# osh_bga_test.net
KiCad netlist of a schematic drawn in EAGLE
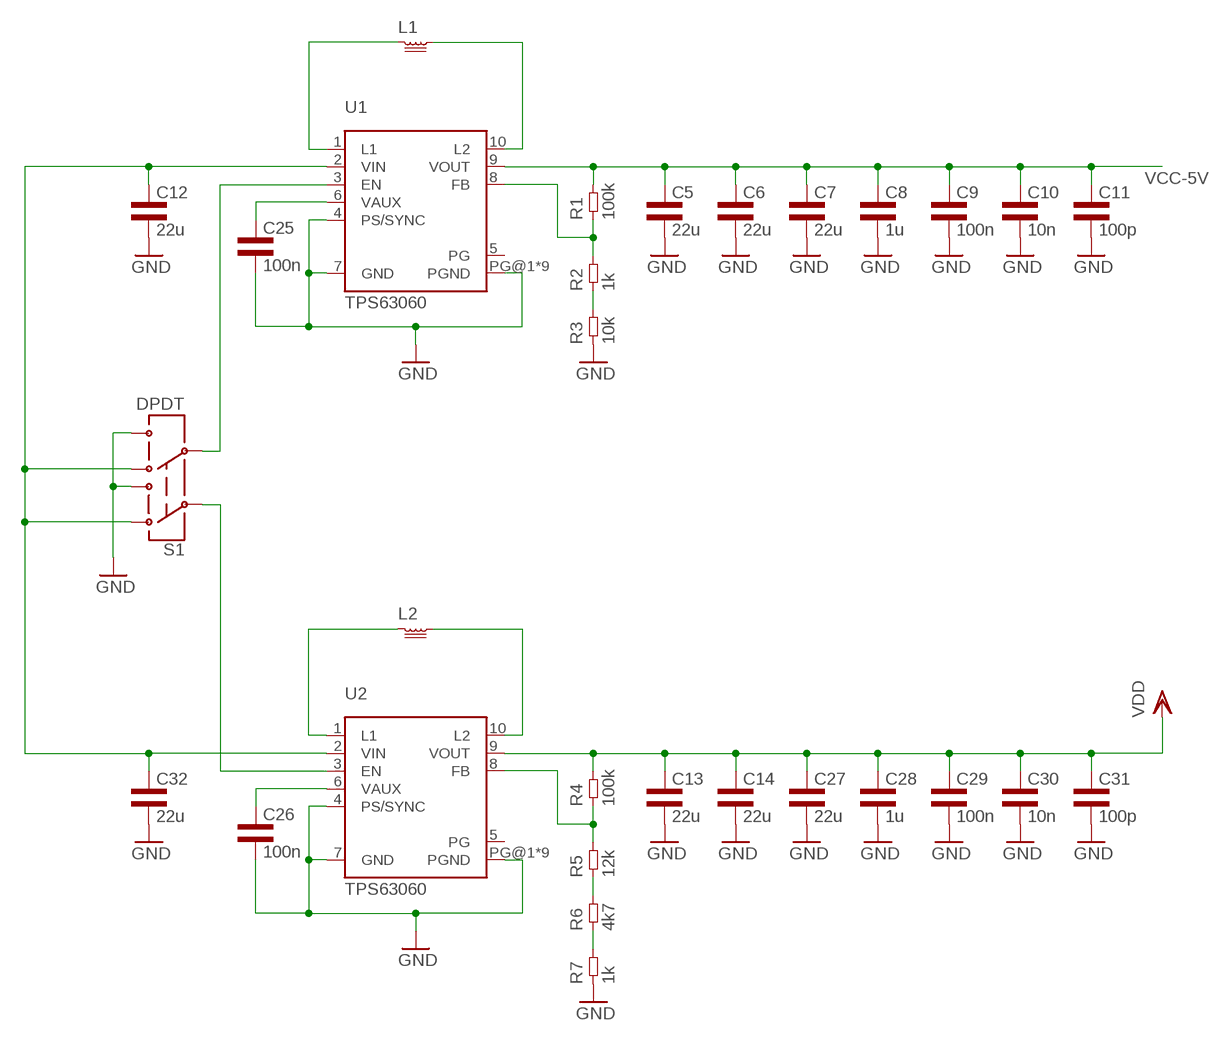
[diagram p0: schematic, sheet 1]
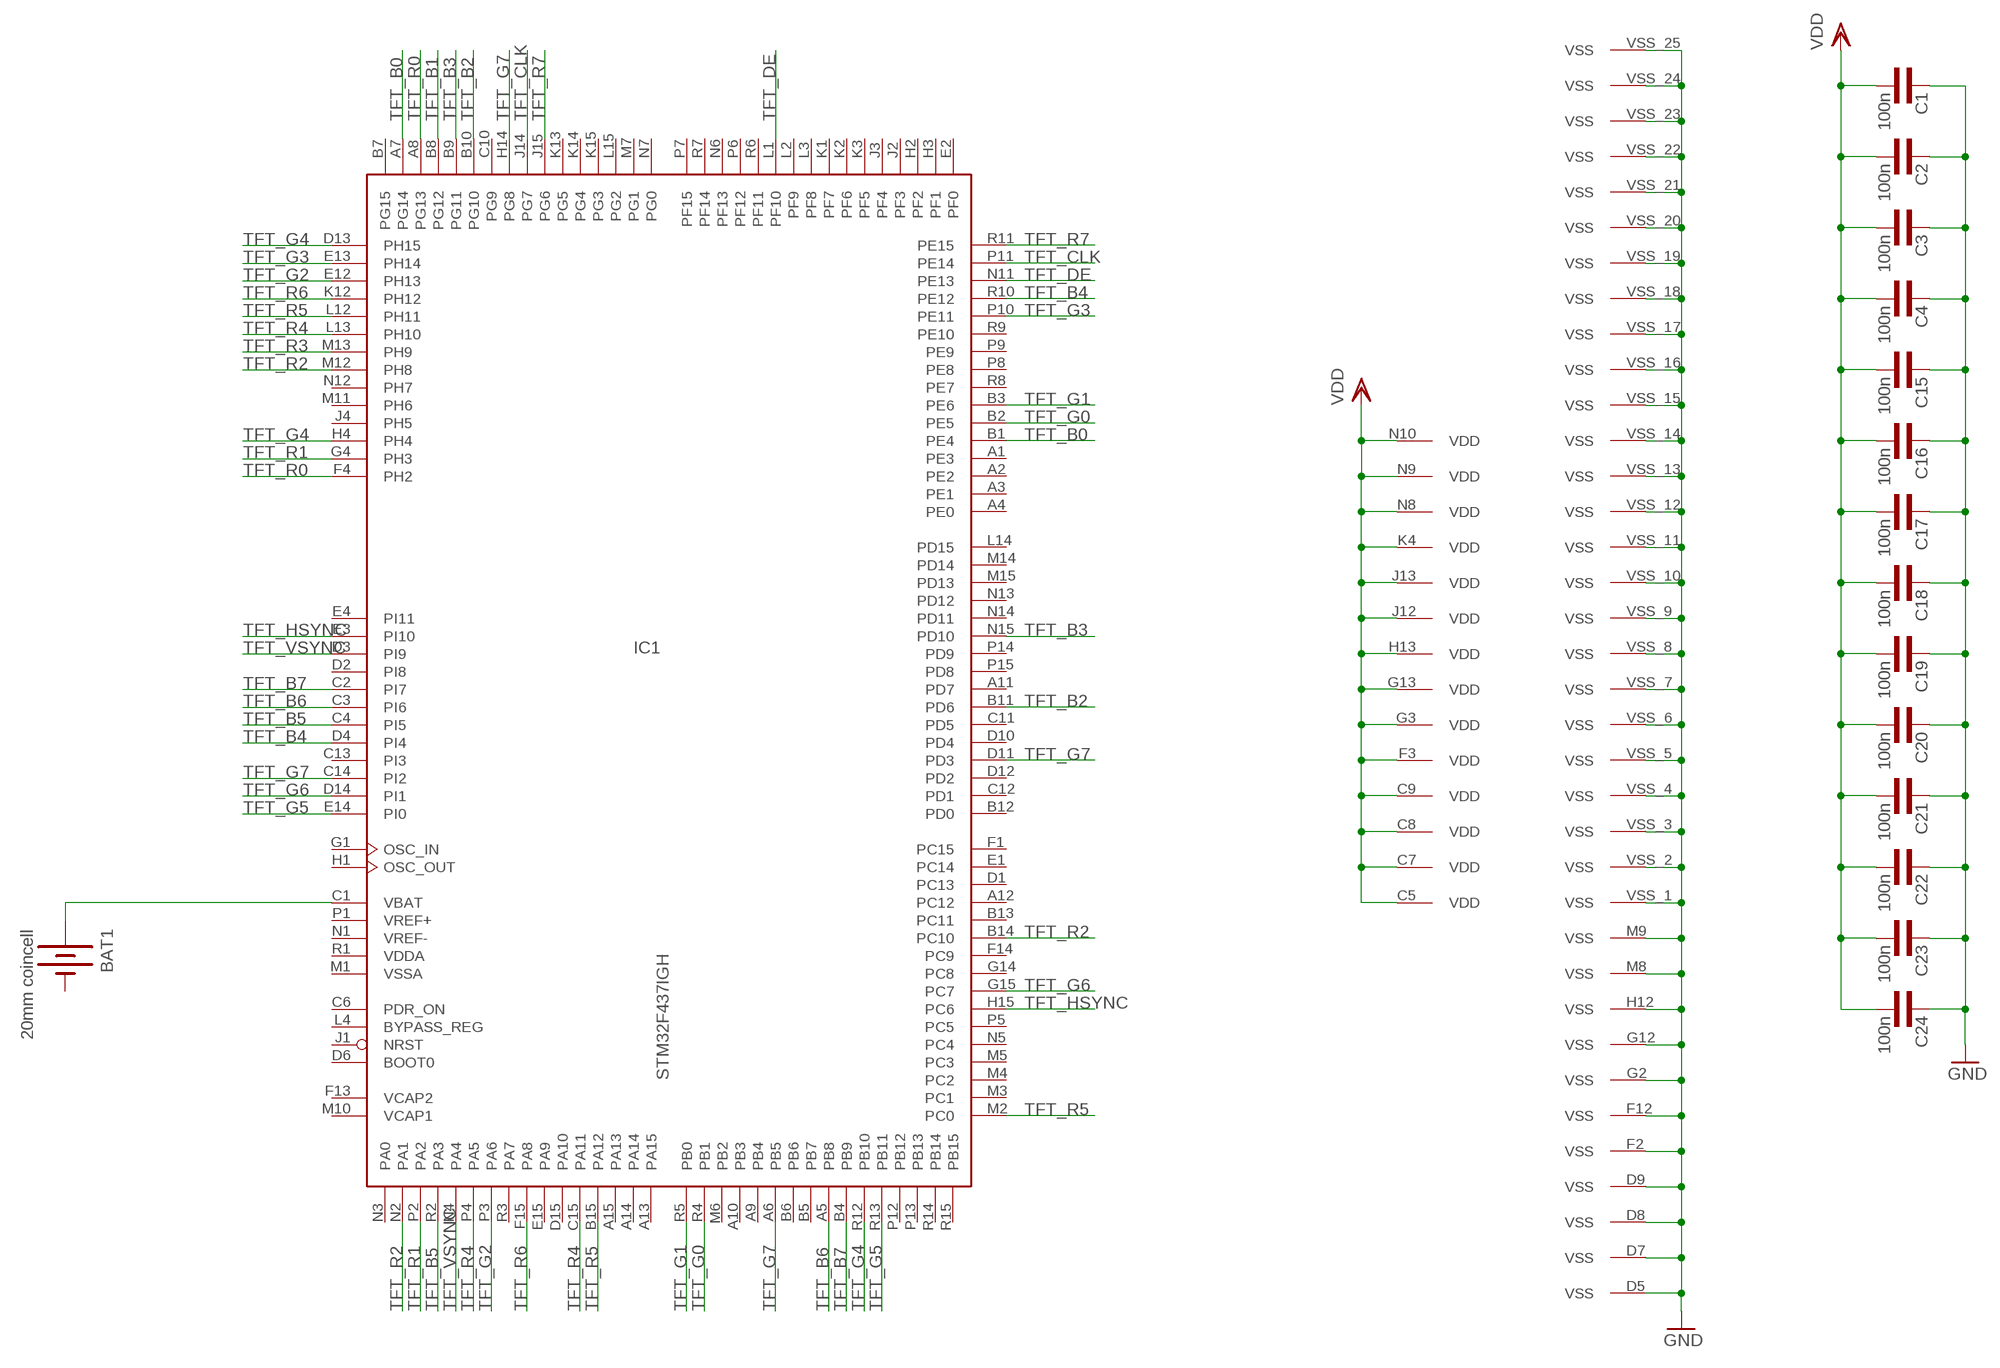
[diagram p1: schematic, sheet 2]
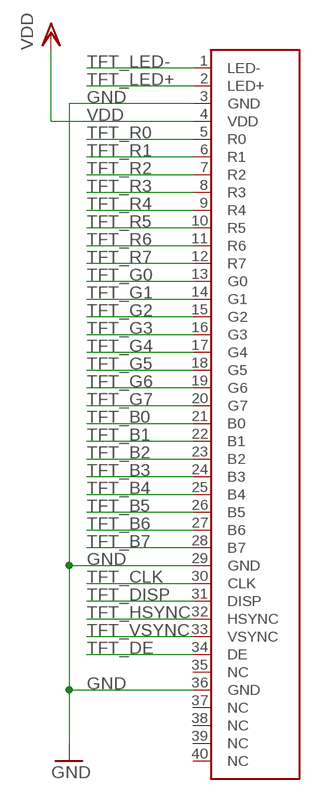
[diagram p2: schematic, sheet 3]
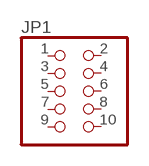
[diagram p3: schematic, sheet 4]

(export (version "E")
  (design (tool "Eeschema 10.0.6"))
  (components
    (comp (ref "C5")
      (value "22u")
      (footprint "eagle-import:1206L3")
      (libsource (lib "eagle-import") (part "CAP1206L3"))
    )
    (comp (ref "C6")
      (value "22u")
      (footprint "eagle-import:1206L3")
      (libsource (lib "eagle-import") (part "CAP1206L3"))
    )
    (comp (ref "C7")
      (value "22u")
      (footprint "eagle-import:1206L3")
      (libsource (lib "eagle-import") (part "CAP1206L3"))
    )
    (comp (ref "C8")
      (value "1u")
      (footprint "eagle-import:0805L3")
      (libsource (lib "eagle-import") (part "CAP0805L3"))
    )
    (comp (ref "C9")
      (value "100n")
      (footprint "eagle-import:0603L3")
      (libsource (lib "eagle-import") (part "CAP0603L3"))
    )
    (comp (ref "C10")
      (value "10n")
      (footprint "eagle-import:0603L3")
      (libsource (lib "eagle-import") (part "CAP0603L3"))
    )
    (comp (ref "C11")
      (value "100p")
      (footprint "eagle-import:0603L3")
      (libsource (lib "eagle-import") (part "CAP0603L3"))
    )
    (comp (ref "C12")
      (value "22u")
      (footprint "eagle-import:1206L3")
      (libsource (lib "eagle-import") (part "CAP1206L3"))
    )
    (comp (ref "C13")
      (value "22u")
      (footprint "eagle-import:1206L3")
      (libsource (lib "eagle-import") (part "CAP1206L3"))
    )
    (comp (ref "C14")
      (value "22u")
      (footprint "eagle-import:1206L3")
      (libsource (lib "eagle-import") (part "CAP1206L3"))
    )
    (comp (ref "C25")
      (value "100n")
      (footprint "eagle-import:0603L3")
      (libsource (lib "eagle-import") (part "CAP0603L3"))
    )
    (comp (ref "C26")
      (value "100n")
      (footprint "eagle-import:0603L3")
      (libsource (lib "eagle-import") (part "CAP0603L3"))
    )
    (comp (ref "C27")
      (value "22u")
      (footprint "eagle-import:1206L3")
      (libsource (lib "eagle-import") (part "CAP1206L3"))
    )
    (comp (ref "C28")
      (value "1u")
      (footprint "eagle-import:0805L3")
      (libsource (lib "eagle-import") (part "CAP0805L3"))
    )
    (comp (ref "C29")
      (value "100n")
      (footprint "eagle-import:0603L3")
      (libsource (lib "eagle-import") (part "CAP0603L3"))
    )
    (comp (ref "C30")
      (value "10n")
      (footprint "eagle-import:0603L3")
      (libsource (lib "eagle-import") (part "CAP0603L3"))
    )
    (comp (ref "C31")
      (value "100p")
      (footprint "eagle-import:0603L3")
      (libsource (lib "eagle-import") (part "CAP0603L3"))
    )
    (comp (ref "C32")
      (value "22u")
      (footprint "eagle-import:1206L3")
      (libsource (lib "eagle-import") (part "CAP1206L3"))
    )
    (comp (ref "L1")
      (value "INDUCTORSRP4020")
      (footprint "eagle-import:SRP4020")
      (libsource (lib "eagle-import") (part "INDUCTORSRP4020"))
    )
    (comp (ref "L2")
      (value "INDUCTORSRP4020")
      (footprint "eagle-import:SRP4020")
      (libsource (lib "eagle-import") (part "INDUCTORSRP4020"))
    )
    (comp (ref "R1")
      (value "100k")
      (footprint "eagle-import:0603L3")
      (libsource (lib "eagle-import") (part "RES0603L3"))
    )
    (comp (ref "R2")
      (value "1k")
      (footprint "eagle-import:0603L3")
      (libsource (lib "eagle-import") (part "RES0603L3"))
    )
    (comp (ref "R3")
      (value "10k")
      (footprint "eagle-import:0603L3")
      (libsource (lib "eagle-import") (part "RES0603L3"))
    )
    (comp (ref "R4")
      (value "100k")
      (footprint "eagle-import:0603L3")
      (libsource (lib "eagle-import") (part "RES0603L3"))
    )
    (comp (ref "R5")
      (value "12k")
      (footprint "eagle-import:0603L3")
      (libsource (lib "eagle-import") (part "RES0603L3"))
    )
    (comp (ref "R6")
      (value "4k7")
      (footprint "eagle-import:0603L3")
      (libsource (lib "eagle-import") (part "RES0603L3"))
    )
    (comp (ref "R7")
      (value "1k")
      (footprint "eagle-import:0603L3")
      (libsource (lib "eagle-import") (part "RES0603L3"))
    )
    (comp (ref "S1")
      (value "DPDT")
      (footprint "eagle-import:AYZ0202")
      (libsource (lib "eagle-import") (part "SWITCH-DPDTAYZ0202"))
    )
    (comp (ref "U1")
      (value "TPS63060")
      (footprint "eagle-import:S-PWSON-N10")
      (libsource (lib "eagle-import") (part "TPS63060"))
    )
    (comp (ref "U2")
      (value "TPS63060")
      (footprint "eagle-import:S-PWSON-N10")
      (libsource (lib "eagle-import") (part "TPS63060"))
    )
    (comp (ref "BAT1")
      (value "20mm coincell")
      (footprint "eagle-import:BATTCON_20MM_4LEGS")
      (libsource (lib "eagle-import") (part "BATTERY20MM_4LEGS"))
    )
    (comp (ref "C1")
      (value "100n")
      (footprint "eagle-import:0402L3")
      (libsource (lib "eagle-import") (part "CAP0402L3"))
    )
    (comp (ref "C2")
      (value "100n")
      (footprint "eagle-import:0402L3")
      (libsource (lib "eagle-import") (part "CAP0402L3"))
    )
    (comp (ref "C3")
      (value "100n")
      (footprint "eagle-import:0402L3")
      (libsource (lib "eagle-import") (part "CAP0402L3"))
    )
    (comp (ref "C4")
      (value "100n")
      (footprint "eagle-import:0402L3")
      (libsource (lib "eagle-import") (part "CAP0402L3"))
    )
    (comp (ref "C15")
      (value "100n")
      (footprint "eagle-import:0402L3")
      (libsource (lib "eagle-import") (part "CAP0402L3"))
    )
    (comp (ref "C16")
      (value "100n")
      (footprint "eagle-import:0402L3")
      (libsource (lib "eagle-import") (part "CAP0402L3"))
    )
    (comp (ref "C17")
      (value "100n")
      (footprint "eagle-import:0402L3")
      (libsource (lib "eagle-import") (part "CAP0402L3"))
    )
    (comp (ref "C18")
      (value "100n")
      (footprint "eagle-import:0402L3")
      (libsource (lib "eagle-import") (part "CAP0402L3"))
    )
    (comp (ref "C19")
      (value "100n")
      (footprint "eagle-import:0402L3")
      (libsource (lib "eagle-import") (part "CAP0402L3"))
    )
    (comp (ref "C20")
      (value "100n")
      (footprint "eagle-import:0402L3")
      (libsource (lib "eagle-import") (part "CAP0402L3"))
    )
    (comp (ref "C21")
      (value "100n")
      (footprint "eagle-import:0402L3")
      (libsource (lib "eagle-import") (part "CAP0402L3"))
    )
    (comp (ref "C22")
      (value "100n")
      (footprint "eagle-import:0402L3")
      (libsource (lib "eagle-import") (part "CAP0402L3"))
    )
    (comp (ref "C23")
      (value "100n")
      (footprint "eagle-import:0402L3")
      (libsource (lib "eagle-import") (part "CAP0402L3"))
    )
    (comp (ref "C24")
      (value "100n")
      (footprint "eagle-import:0402L3")
      (libsource (lib "eagle-import") (part "CAP0402L3"))
    )
    (comp (ref "IC1")
      (value "STM32F437IGH")
      (footprint "eagle-import:UFBGA176+25")
      (libsource (lib "eagle-import") (part "STM32F437IHG"))
    )
    (comp (ref "JP1")
      (value "PINHD-2X5")
      (footprint "eagle-import:2X05")
      (libsource (lib "eagle-import") (part "PINHD-2X5"))
    )
    (comp (ref "CON1")
      (value "NH-4.3")
      (footprint "eagle-import:FPC-40")
      (libsource (lib "eagle-import") (part "NH-4.3"))
    )
  )
  (nets
    (net (code "1") (name "-") (class "Default")
      (node (ref "BAT1") (pin "2") (pinfunction "-_2") (pintype "power_in"))
    )
    (net (code "2") (name "GND") (class "Default")
      (node (ref "C1") (pin "P$1") (pinfunction "1_P$1") (pintype "bidirectional"))
      (node (ref "C10") (pin "P$2") (pinfunction "2_P$2") (pintype "bidirectional"))
      (node (ref "C11") (pin "P$2") (pinfunction "2_P$2") (pintype "bidirectional"))
      (node (ref "C12") (pin "2") (pinfunction "2_2") (pintype "bidirectional"))
      (node (ref "C13") (pin "2") (pinfunction "2_2") (pintype "bidirectional"))
      (node (ref "C14") (pin "2") (pinfunction "2_2") (pintype "bidirectional"))
      (node (ref "C15") (pin "P$1") (pinfunction "1_P$1") (pintype "bidirectional"))
      (node (ref "C16") (pin "P$1") (pinfunction "1_P$1") (pintype "bidirectional"))
      (node (ref "C17") (pin "P$1") (pinfunction "1_P$1") (pintype "bidirectional"))
      (node (ref "C18") (pin "P$1") (pinfunction "1_P$1") (pintype "bidirectional"))
      (node (ref "C19") (pin "P$1") (pinfunction "1_P$1") (pintype "bidirectional"))
      (node (ref "C2") (pin "P$1") (pinfunction "1_P$1") (pintype "bidirectional"))
      (node (ref "C20") (pin "P$1") (pinfunction "1_P$1") (pintype "bidirectional"))
      (node (ref "C21") (pin "P$1") (pinfunction "1_P$1") (pintype "bidirectional"))
      (node (ref "C22") (pin "P$1") (pinfunction "1_P$1") (pintype "bidirectional"))
      (node (ref "C23") (pin "P$1") (pinfunction "1_P$1") (pintype "bidirectional"))
      (node (ref "C24") (pin "P$1") (pinfunction "1_P$1") (pintype "bidirectional"))
      (node (ref "C25") (pin "P$2") (pinfunction "2_P$2") (pintype "bidirectional"))
      (node (ref "C26") (pin "P$2") (pinfunction "2_P$2") (pintype "bidirectional"))
      (node (ref "C27") (pin "2") (pinfunction "2_2") (pintype "bidirectional"))
      (node (ref "C28") (pin "2") (pinfunction "2_2") (pintype "bidirectional"))
      (node (ref "C29") (pin "P$2") (pinfunction "2_P$2") (pintype "bidirectional"))
      (node (ref "C3") (pin "P$1") (pinfunction "1_P$1") (pintype "bidirectional"))
      (node (ref "C30") (pin "P$2") (pinfunction "2_P$2") (pintype "bidirectional"))
      (node (ref "C31") (pin "P$2") (pinfunction "2_P$2") (pintype "bidirectional"))
      (node (ref "C32") (pin "2") (pinfunction "2_2") (pintype "bidirectional"))
      (node (ref "C4") (pin "P$1") (pinfunction "1_P$1") (pintype "bidirectional"))
      (node (ref "C5") (pin "2") (pinfunction "2_2") (pintype "bidirectional"))
      (node (ref "C6") (pin "2") (pinfunction "2_2") (pintype "bidirectional"))
      (node (ref "C7") (pin "2") (pinfunction "2_2") (pintype "bidirectional"))
      (node (ref "C8") (pin "2") (pinfunction "2_2") (pintype "bidirectional"))
      (node (ref "C9") (pin "P$2") (pinfunction "2_P$2") (pintype "bidirectional"))
      (node (ref "CON1") (pin "29") (pinfunction "GND_29") (pintype "bidirectional"))
      (node (ref "CON1") (pin "3") (pinfunction "GND_3") (pintype "bidirectional"))
      (node (ref "CON1") (pin "36") (pinfunction "GND_36") (pintype "bidirectional"))
      (node (ref "IC1") (pin "D5") (pinfunction "VSS_D5") (pintype "power_in"))
      (node (ref "IC1") (pin "D7") (pinfunction "VSS_D7") (pintype "power_in"))
      (node (ref "IC1") (pin "D8") (pinfunction "VSS_D8") (pintype "power_in"))
      (node (ref "IC1") (pin "D9") (pinfunction "VSS_D9") (pintype "power_in"))
      (node (ref "IC1") (pin "F12") (pinfunction "VSS_F12") (pintype "power_in"))
      (node (ref "IC1") (pin "F2") (pinfunction "VSS_F2") (pintype "power_in"))
      (node (ref "IC1") (pin "G12") (pinfunction "VSS_G12") (pintype "power_in"))
      (node (ref "IC1") (pin "G2") (pinfunction "VSS_G2") (pintype "power_in"))
      (node (ref "IC1") (pin "H12") (pinfunction "VSS_H12") (pintype "power_in"))
      (node (ref "IC1") (pin "M8") (pinfunction "VSS_M8") (pintype "power_in"))
      (node (ref "IC1") (pin "M9") (pinfunction "VSS_M9") (pintype "power_in"))
      (node (ref "IC1") (pin "VSS_1") (pinfunction "VSS_VSS_1") (pintype "power_in"))
      (node (ref "IC1") (pin "VSS_10") (pinfunction "VSS_VSS_10") (pintype "power_in"))
      (node (ref "IC1") (pin "VSS_11") (pinfunction "VSS_VSS_11") (pintype "power_in"))
      (node (ref "IC1") (pin "VSS_12") (pinfunction "VSS_VSS_12") (pintype "power_in"))
      (node (ref "IC1") (pin "VSS_13") (pinfunction "VSS_VSS_13") (pintype "power_in"))
      (node (ref "IC1") (pin "VSS_14") (pinfunction "VSS_VSS_14") (pintype "power_in"))
      (node (ref "IC1") (pin "VSS_15") (pinfunction "VSS_VSS_15") (pintype "power_in"))
      (node (ref "IC1") (pin "VSS_16") (pinfunction "VSS_VSS_16") (pintype "power_in"))
      (node (ref "IC1") (pin "VSS_17") (pinfunction "VSS_VSS_17") (pintype "power_in"))
      (node (ref "IC1") (pin "VSS_18") (pinfunction "VSS_VSS_18") (pintype "power_in"))
      (node (ref "IC1") (pin "VSS_19") (pinfunction "VSS_VSS_19") (pintype "power_in"))
      (node (ref "IC1") (pin "VSS_2") (pinfunction "VSS_VSS_2") (pintype "power_in"))
      (node (ref "IC1") (pin "VSS_20") (pinfunction "VSS_VSS_20") (pintype "power_in"))
      (node (ref "IC1") (pin "VSS_21") (pinfunction "VSS_VSS_21") (pintype "power_in"))
      (node (ref "IC1") (pin "VSS_22") (pinfunction "VSS_VSS_22") (pintype "power_in"))
      (node (ref "IC1") (pin "VSS_23") (pinfunction "VSS_VSS_23") (pintype "power_in"))
      (node (ref "IC1") (pin "VSS_24") (pinfunction "VSS_VSS_24") (pintype "power_in"))
      (node (ref "IC1") (pin "VSS_25") (pinfunction "VSS_VSS_25") (pintype "power_in"))
      (node (ref "IC1") (pin "VSS_3") (pinfunction "VSS_VSS_3") (pintype "power_in"))
      (node (ref "IC1") (pin "VSS_4") (pinfunction "VSS_VSS_4") (pintype "power_in"))
      (node (ref "IC1") (pin "VSS_5") (pinfunction "VSS_VSS_5") (pintype "power_in"))
      (node (ref "IC1") (pin "VSS_6") (pinfunction "VSS_VSS_6") (pintype "power_in"))
      (node (ref "IC1") (pin "VSS_7") (pinfunction "VSS_VSS_7") (pintype "power_in"))
      (node (ref "IC1") (pin "VSS_8") (pinfunction "VSS_VSS_8") (pintype "power_in"))
      (node (ref "IC1") (pin "VSS_9") (pinfunction "VSS_VSS_9") (pintype "power_in"))
      (node (ref "R3") (pin "P$1") (pinfunction "1_P$1") (pintype "bidirectional"))
      (node (ref "R7") (pin "P$1") (pinfunction "1_P$1") (pintype "bidirectional"))
      (node (ref "S1") (pin "3") (pinfunction "3_3") (pintype "bidirectional"))
      (node (ref "S1") (pin "6") (pinfunction "6_6") (pintype "bidirectional"))
      (node (ref "U1") (pin "4") (pinfunction "PS/SYNC_4") (pintype "bidirectional"))
      (node (ref "U1") (pin "7") (pinfunction "GND_7") (pintype "bidirectional"))
      (node (ref "U1") (pin "PG@1") (pinfunction "PGND_PG@1") (pintype "bidirectional"))
      (node (ref "U1") (pin "PG@2") (pinfunction "PGND_PG@2") (pintype "bidirectional"))
      (node (ref "U1") (pin "PG@3") (pinfunction "PGND_PG@3") (pintype "bidirectional"))
      (node (ref "U1") (pin "PG@4") (pinfunction "PGND_PG@4") (pintype "bidirectional"))
      (node (ref "U1") (pin "PG@5") (pinfunction "PGND_PG@5") (pintype "bidirectional"))
      (node (ref "U1") (pin "PG@6") (pinfunction "PGND_PG@6") (pintype "bidirectional"))
      (node (ref "U1") (pin "PG@7") (pinfunction "PGND_PG@7") (pintype "bidirectional"))
      (node (ref "U1") (pin "PG@8") (pinfunction "PGND_PG@8") (pintype "bidirectional"))
      (node (ref "U1") (pin "PG@9") (pinfunction "PGND_PG@9") (pintype "bidirectional"))
      (node (ref "U2") (pin "4") (pinfunction "PS/SYNC_4") (pintype "bidirectional"))
      (node (ref "U2") (pin "7") (pinfunction "GND_7") (pintype "bidirectional"))
      (node (ref "U2") (pin "PG@1") (pinfunction "PGND_PG@1") (pintype "bidirectional"))
      (node (ref "U2") (pin "PG@2") (pinfunction "PGND_PG@2") (pintype "bidirectional"))
      (node (ref "U2") (pin "PG@3") (pinfunction "PGND_PG@3") (pintype "bidirectional"))
      (node (ref "U2") (pin "PG@4") (pinfunction "PGND_PG@4") (pintype "bidirectional"))
      (node (ref "U2") (pin "PG@5") (pinfunction "PGND_PG@5") (pintype "bidirectional"))
      (node (ref "U2") (pin "PG@6") (pinfunction "PGND_PG@6") (pintype "bidirectional"))
      (node (ref "U2") (pin "PG@7") (pinfunction "PGND_PG@7") (pintype "bidirectional"))
      (node (ref "U2") (pin "PG@8") (pinfunction "PGND_PG@8") (pintype "bidirectional"))
      (node (ref "U2") (pin "PG@9") (pinfunction "PGND_PG@9") (pintype "bidirectional"))
    )
    (net (code "3") (name "Net-(BAT1-+)") (class "Default")
      (node (ref "BAT1") (pin "1") (pinfunction "+_1") (pintype "power_in"))
      (node (ref "IC1") (pin "C1") (pinfunction "VBAT_C1") (pintype "power_in"))
    )
    (net (code "4") (name "Net-(C25-1)") (class "Default")
      (node (ref "C25") (pin "P$1") (pinfunction "1_P$1") (pintype "bidirectional"))
      (node (ref "U1") (pin "6") (pinfunction "VAUX_6") (pintype "bidirectional"))
    )
    (net (code "5") (name "Net-(C26-1)") (class "Default")
      (node (ref "C26") (pin "P$1") (pinfunction "1_P$1") (pintype "bidirectional"))
      (node (ref "U2") (pin "6") (pinfunction "VAUX_6") (pintype "bidirectional"))
    )
    (net (code "6") (name "Net-(R1-1)") (class "Default")
      (node (ref "R1") (pin "P$1") (pinfunction "1_P$1") (pintype "bidirectional"))
      (node (ref "R2") (pin "P$2") (pinfunction "2_P$2") (pintype "bidirectional"))
      (node (ref "U1") (pin "8") (pinfunction "FB_8") (pintype "bidirectional"))
    )
    (net (code "7") (name "Net-(R2-1)") (class "Default")
      (node (ref "R2") (pin "P$1") (pinfunction "1_P$1") (pintype "bidirectional"))
      (node (ref "R3") (pin "P$2") (pinfunction "2_P$2") (pintype "bidirectional"))
    )
    (net (code "8") (name "Net-(R4-1)") (class "Default")
      (node (ref "R4") (pin "P$1") (pinfunction "1_P$1") (pintype "bidirectional"))
      (node (ref "R5") (pin "P$2") (pinfunction "2_P$2") (pintype "bidirectional"))
      (node (ref "U2") (pin "8") (pinfunction "FB_8") (pintype "bidirectional"))
    )
    (net (code "9") (name "Net-(R5-1)") (class "Default")
      (node (ref "R5") (pin "P$1") (pinfunction "1_P$1") (pintype "bidirectional"))
      (node (ref "R6") (pin "P$2") (pinfunction "2_P$2") (pintype "bidirectional"))
    )
    (net (code "10") (name "Net-(R6-1)") (class "Default")
      (node (ref "R6") (pin "P$1") (pinfunction "1_P$1") (pintype "bidirectional"))
      (node (ref "R7") (pin "P$2") (pinfunction "2_P$2") (pintype "bidirectional"))
    )
    (net (code "11") (name "Net-(U1-EN)") (class "Default")
      (node (ref "S1") (pin "5") (pinfunction "5_5") (pintype "bidirectional"))
      (node (ref "U1") (pin "3") (pinfunction "EN_3") (pintype "bidirectional"))
    )
    (net (code "12") (name "Net-(U1-L1)") (class "Default")
      (node (ref "L1") (pin "1") (pinfunction "1_1") (pintype "bidirectional"))
      (node (ref "U1") (pin "1") (pinfunction "L1_1") (pintype "bidirectional"))
    )
    (net (code "13") (name "Net-(U1-L2)") (class "Default")
      (node (ref "L1") (pin "2") (pinfunction "2_2") (pintype "bidirectional"))
      (node (ref "U1") (pin "10") (pinfunction "L2_10") (pintype "bidirectional"))
    )
    (net (code "14") (name "Net-(U1-VIN)") (class "Default")
      (node (ref "C12") (pin "1") (pinfunction "1_1") (pintype "bidirectional"))
      (node (ref "C32") (pin "1") (pinfunction "1_1") (pintype "bidirectional"))
      (node (ref "S1") (pin "1") (pinfunction "1_1") (pintype "bidirectional"))
      (node (ref "S1") (pin "4") (pinfunction "4_4") (pintype "bidirectional"))
      (node (ref "U1") (pin "2") (pinfunction "VIN_2") (pintype "bidirectional"))
      (node (ref "U2") (pin "2") (pinfunction "VIN_2") (pintype "bidirectional"))
    )
    (net (code "15") (name "Net-(U2-EN)") (class "Default")
      (node (ref "S1") (pin "2") (pinfunction "2_2") (pintype "bidirectional"))
      (node (ref "U2") (pin "3") (pinfunction "EN_3") (pintype "bidirectional"))
    )
    (net (code "16") (name "Net-(U2-L1)") (class "Default")
      (node (ref "L2") (pin "1") (pinfunction "1_1") (pintype "bidirectional"))
      (node (ref "U2") (pin "1") (pinfunction "L1_1") (pintype "bidirectional"))
    )
    (net (code "17") (name "Net-(U2-L2)") (class "Default")
      (node (ref "L2") (pin "2") (pinfunction "2_2") (pintype "bidirectional"))
      (node (ref "U2") (pin "10") (pinfunction "L2_10") (pintype "bidirectional"))
    )
    (net (code "18") (name "TFT_B0") (class "Default")
      (node (ref "CON1") (pin "21") (pinfunction "B0_21") (pintype "bidirectional"))
      (node (ref "IC1") (pin "A7") (pinfunction "PG14_A7") (pintype "bidirectional"))
      (node (ref "IC1") (pin "B1") (pinfunction "PE4_B1") (pintype "bidirectional"))
    )
    (net (code "19") (name "TFT_B1") (class "Default")
      (node (ref "CON1") (pin "22") (pinfunction "B1_22") (pintype "bidirectional"))
      (node (ref "IC1") (pin "B8") (pinfunction "PG12_B8") (pintype "bidirectional"))
    )
    (net (code "20") (name "TFT_B2") (class "Default")
      (node (ref "CON1") (pin "23") (pinfunction "B2_23") (pintype "bidirectional"))
      (node (ref "IC1") (pin "B10") (pinfunction "PG10_B10") (pintype "bidirectional"))
      (node (ref "IC1") (pin "B11") (pinfunction "PD6_B11") (pintype "bidirectional"))
    )
    (net (code "21") (name "TFT_B3") (class "Default")
      (node (ref "CON1") (pin "24") (pinfunction "B3_24") (pintype "bidirectional"))
      (node (ref "IC1") (pin "B9") (pinfunction "PG11_B9") (pintype "bidirectional"))
      (node (ref "IC1") (pin "N15") (pinfunction "PD10_N15") (pintype "bidirectional"))
    )
    (net (code "22") (name "TFT_B4") (class "Default")
      (node (ref "CON1") (pin "25") (pinfunction "B4_25") (pintype "bidirectional"))
      (node (ref "IC1") (pin "D4") (pinfunction "PI4_D4") (pintype "bidirectional"))
      (node (ref "IC1") (pin "R10") (pinfunction "PE12_R10") (pintype "bidirectional"))
    )
    (net (code "23") (name "TFT_B5") (class "Default")
      (node (ref "CON1") (pin "26") (pinfunction "B5_26") (pintype "bidirectional"))
      (node (ref "IC1") (pin "C4") (pinfunction "PI5_C4") (pintype "bidirectional"))
      (node (ref "IC1") (pin "R2") (pinfunction "PA3_R2") (pintype "bidirectional"))
    )
    (net (code "24") (name "TFT_B6") (class "Default")
      (node (ref "CON1") (pin "27") (pinfunction "B6_27") (pintype "bidirectional"))
      (node (ref "IC1") (pin "A5") (pinfunction "PB8_A5") (pintype "bidirectional"))
      (node (ref "IC1") (pin "C3") (pinfunction "PI6_C3") (pintype "bidirectional"))
    )
    (net (code "25") (name "TFT_B7") (class "Default")
      (node (ref "CON1") (pin "28") (pinfunction "B7_28") (pintype "bidirectional"))
      (node (ref "IC1") (pin "B4") (pinfunction "PB9_B4") (pintype "bidirectional"))
      (node (ref "IC1") (pin "C2") (pinfunction "PI7_C2") (pintype "bidirectional"))
    )
    (net (code "26") (name "TFT_CLK") (class "Default")
      (node (ref "CON1") (pin "30") (pinfunction "CLK_30") (pintype "bidirectional"))
      (node (ref "IC1") (pin "J14") (pinfunction "PG7_J14") (pintype "bidirectional"))
      (node (ref "IC1") (pin "P11") (pinfunction "PE14_P11") (pintype "bidirectional"))
    )
    (net (code "27") (name "TFT_DE") (class "Default")
      (node (ref "CON1") (pin "34") (pinfunction "DE_34") (pintype "bidirectional"))
      (node (ref "IC1") (pin "L1") (pinfunction "PF10_L1") (pintype "bidirectional"))
      (node (ref "IC1") (pin "N11") (pinfunction "PE13_N11") (pintype "bidirectional"))
    )
    (net (code "28") (name "TFT_DISP") (class "Default")
      (node (ref "CON1") (pin "31") (pinfunction "DISP_31") (pintype "bidirectional"))
    )
    (net (code "29") (name "TFT_G0") (class "Default")
      (node (ref "CON1") (pin "13") (pinfunction "G0_13") (pintype "bidirectional"))
      (node (ref "IC1") (pin "B2") (pinfunction "PE5_B2") (pintype "bidirectional"))
      (node (ref "IC1") (pin "R4") (pinfunction "PB1_R4") (pintype "bidirectional"))
    )
    (net (code "30") (name "TFT_G1") (class "Default")
      (node (ref "CON1") (pin "14") (pinfunction "G1_14") (pintype "bidirectional"))
      (node (ref "IC1") (pin "B3") (pinfunction "PE6_B3") (pintype "bidirectional"))
      (node (ref "IC1") (pin "R5") (pinfunction "PB0_R5") (pintype "bidirectional"))
    )
    (net (code "31") (name "TFT_G2") (class "Default")
      (node (ref "CON1") (pin "15") (pinfunction "G2_15") (pintype "bidirectional"))
      (node (ref "IC1") (pin "E12") (pinfunction "PH13_E12") (pintype "bidirectional"))
      (node (ref "IC1") (pin "P3") (pinfunction "PA6_P3") (pintype "bidirectional"))
    )
    (net (code "32") (name "TFT_G3") (class "Default")
      (node (ref "CON1") (pin "16") (pinfunction "G3_16") (pintype "bidirectional"))
      (node (ref "IC1") (pin "E13") (pinfunction "PH14_E13") (pintype "bidirectional"))
      (node (ref "IC1") (pin "P10") (pinfunction "PE11_P10") (pintype "bidirectional"))
    )
    (net (code "33") (name "TFT_G4") (class "Default")
      (node (ref "CON1") (pin "17") (pinfunction "G4_17") (pintype "bidirectional"))
      (node (ref "IC1") (pin "D13") (pinfunction "PH15_D13") (pintype "bidirectional"))
      (node (ref "IC1") (pin "H4") (pinfunction "PH4_H4") (pintype "bidirectional"))
      (node (ref "IC1") (pin "R12") (pinfunction "PB10_R12") (pintype "bidirectional"))
    )
    (net (code "34") (name "TFT_G5") (class "Default")
      (node (ref "CON1") (pin "18") (pinfunction "G5_18") (pintype "bidirectional"))
      (node (ref "IC1") (pin "E14") (pinfunction "PI0_E14") (pintype "bidirectional"))
      (node (ref "IC1") (pin "R13") (pinfunction "PB11_R13") (pintype "bidirectional"))
    )
    (net (code "35") (name "TFT_G6") (class "Default")
      (node (ref "CON1") (pin "19") (pinfunction "G6_19") (pintype "bidirectional"))
      (node (ref "IC1") (pin "D14") (pinfunction "PI1_D14") (pintype "bidirectional"))
      (node (ref "IC1") (pin "G15") (pinfunction "PC7_G15") (pintype "bidirectional"))
    )
    (net (code "36") (name "TFT_G7") (class "Default")
      (node (ref "CON1") (pin "20") (pinfunction "G7_20") (pintype "bidirectional"))
      (node (ref "IC1") (pin "A6") (pinfunction "PB5_A6") (pintype "bidirectional"))
      (node (ref "IC1") (pin "C14") (pinfunction "PI2_C14") (pintype "bidirectional"))
      (node (ref "IC1") (pin "D11") (pinfunction "PD3_D11") (pintype "bidirectional"))
      (node (ref "IC1") (pin "H14") (pinfunction "PG8_H14") (pintype "bidirectional"))
    )
    (net (code "37") (name "TFT_HSYNC") (class "Default")
      (node (ref "CON1") (pin "32") (pinfunction "HSYNC_32") (pintype "bidirectional"))
      (node (ref "IC1") (pin "E3") (pinfunction "PI10_E3") (pintype "bidirectional"))
      (node (ref "IC1") (pin "H15") (pinfunction "PC6_H15") (pintype "bidirectional"))
    )
    (net (code "38") (name "TFT_LED+") (class "Default")
      (node (ref "CON1") (pin "2") (pinfunction "LED+_2") (pintype "bidirectional"))
    )
    (net (code "39") (name "TFT_LED-") (class "Default")
      (node (ref "CON1") (pin "1") (pinfunction "LED-_1") (pintype "bidirectional"))
    )
    (net (code "40") (name "TFT_R0") (class "Default")
      (node (ref "CON1") (pin "5") (pinfunction "R0_5") (pintype "bidirectional"))
      (node (ref "IC1") (pin "A8") (pinfunction "PG13_A8") (pintype "bidirectional"))
      (node (ref "IC1") (pin "F4") (pinfunction "PH2_F4") (pintype "bidirectional"))
    )
    (net (code "41") (name "TFT_R1") (class "Default")
      (node (ref "CON1") (pin "6") (pinfunction "R1_6") (pintype "bidirectional"))
      (node (ref "IC1") (pin "G4") (pinfunction "PH3_G4") (pintype "bidirectional"))
      (node (ref "IC1") (pin "P2") (pinfunction "PA2_P2") (pintype "bidirectional"))
    )
    (net (code "42") (name "TFT_R2") (class "Default")
      (node (ref "CON1") (pin "7") (pinfunction "R2_7") (pintype "bidirectional"))
      (node (ref "IC1") (pin "B14") (pinfunction "PC10_B14") (pintype "bidirectional"))
      (node (ref "IC1") (pin "M12") (pinfunction "PH8_M12") (pintype "bidirectional"))
      (node (ref "IC1") (pin "N2") (pinfunction "PA1_N2") (pintype "bidirectional"))
    )
    (net (code "43") (name "TFT_R3") (class "Default")
      (node (ref "CON1") (pin "8") (pinfunction "R3_8") (pintype "bidirectional"))
      (node (ref "IC1") (pin "M13") (pinfunction "PH9_M13") (pintype "bidirectional"))
    )
    (net (code "44") (name "TFT_R4") (class "Default")
      (node (ref "CON1") (pin "9") (pinfunction "R4_9") (pintype "bidirectional"))
      (node (ref "IC1") (pin "C15") (pinfunction "PA11_C15") (pintype "bidirectional"))
      (node (ref "IC1") (pin "L13") (pinfunction "PH10_L13") (pintype "bidirectional"))
      (node (ref "IC1") (pin "P4") (pinfunction "PA5_P4") (pintype "bidirectional"))
    )
    (net (code "45") (name "TFT_R5") (class "Default")
      (node (ref "CON1") (pin "10") (pinfunction "R5_10") (pintype "bidirectional"))
      (node (ref "IC1") (pin "B15") (pinfunction "PA12_B15") (pintype "bidirectional"))
      (node (ref "IC1") (pin "L12") (pinfunction "PH11_L12") (pintype "bidirectional"))
      (node (ref "IC1") (pin "M2") (pinfunction "PC0_M2") (pintype "bidirectional"))
    )
    (net (code "46") (name "TFT_R6") (class "Default")
      (node (ref "CON1") (pin "11") (pinfunction "R6_11") (pintype "bidirectional"))
      (node (ref "IC1") (pin "F15") (pinfunction "PA8_F15") (pintype "bidirectional"))
      (node (ref "IC1") (pin "K12") (pinfunction "PH12_K12") (pintype "bidirectional"))
    )
    (net (code "47") (name "TFT_R7") (class "Default")
      (node (ref "CON1") (pin "12") (pinfunction "R7_12") (pintype "bidirectional"))
      (node (ref "IC1") (pin "J15") (pinfunction "PG6_J15") (pintype "bidirectional"))
      (node (ref "IC1") (pin "R11") (pinfunction "PE15_R11") (pintype "bidirectional"))
    )
    (net (code "48") (name "TFT_VSYNC") (class "Default")
      (node (ref "CON1") (pin "33") (pinfunction "VSYNC_33") (pintype "bidirectional"))
      (node (ref "IC1") (pin "D3") (pinfunction "PI9_D3") (pintype "bidirectional"))
      (node (ref "IC1") (pin "N4") (pinfunction "PA4_N4") (pintype "bidirectional"))
    )
    (net (code "49") (name "VCAP1") (class "Default")
      (node (ref "IC1") (pin "M10") (pinfunction "VCAP1_M10") (pintype "power_in"))
    )
    (net (code "50") (name "VCAP2") (class "Default")
      (node (ref "IC1") (pin "F13") (pinfunction "VCAP2_F13") (pintype "power_in"))
    )
    (net (code "51") (name "VCC-5V") (class "Default")
      (node (ref "C10") (pin "P$1") (pinfunction "1_P$1") (pintype "bidirectional"))
      (node (ref "C11") (pin "P$1") (pinfunction "1_P$1") (pintype "bidirectional"))
      (node (ref "C5") (pin "1") (pinfunction "1_1") (pintype "bidirectional"))
      (node (ref "C6") (pin "1") (pinfunction "1_1") (pintype "bidirectional"))
      (node (ref "C7") (pin "1") (pinfunction "1_1") (pintype "bidirectional"))
      (node (ref "C8") (pin "1") (pinfunction "1_1") (pintype "bidirectional"))
      (node (ref "C9") (pin "P$1") (pinfunction "1_P$1") (pintype "bidirectional"))
      (node (ref "R1") (pin "P$2") (pinfunction "2_P$2") (pintype "bidirectional"))
      (node (ref "U1") (pin "9") (pinfunction "VOUT_9") (pintype "bidirectional"))
    )
    (net (code "52") (name "VDD") (class "Default")
      (node (ref "C1") (pin "P$2") (pinfunction "2_P$2") (pintype "bidirectional"))
      (node (ref "C13") (pin "1") (pinfunction "1_1") (pintype "bidirectional"))
      (node (ref "C14") (pin "1") (pinfunction "1_1") (pintype "bidirectional"))
      (node (ref "C15") (pin "P$2") (pinfunction "2_P$2") (pintype "bidirectional"))
      (node (ref "C16") (pin "P$2") (pinfunction "2_P$2") (pintype "bidirectional"))
      (node (ref "C17") (pin "P$2") (pinfunction "2_P$2") (pintype "bidirectional"))
      (node (ref "C18") (pin "P$2") (pinfunction "2_P$2") (pintype "bidirectional"))
      (node (ref "C19") (pin "P$2") (pinfunction "2_P$2") (pintype "bidirectional"))
      (node (ref "C2") (pin "P$2") (pinfunction "2_P$2") (pintype "bidirectional"))
      (node (ref "C20") (pin "P$2") (pinfunction "2_P$2") (pintype "bidirectional"))
      (node (ref "C21") (pin "P$2") (pinfunction "2_P$2") (pintype "bidirectional"))
      (node (ref "C22") (pin "P$2") (pinfunction "2_P$2") (pintype "bidirectional"))
      (node (ref "C23") (pin "P$2") (pinfunction "2_P$2") (pintype "bidirectional"))
      (node (ref "C24") (pin "P$2") (pinfunction "2_P$2") (pintype "bidirectional"))
      (node (ref "C27") (pin "1") (pinfunction "1_1") (pintype "bidirectional"))
      (node (ref "C28") (pin "1") (pinfunction "1_1") (pintype "bidirectional"))
      (node (ref "C29") (pin "P$1") (pinfunction "1_P$1") (pintype "bidirectional"))
      (node (ref "C3") (pin "P$2") (pinfunction "2_P$2") (pintype "bidirectional"))
      (node (ref "C30") (pin "P$1") (pinfunction "1_P$1") (pintype "bidirectional"))
      (node (ref "C31") (pin "P$1") (pinfunction "1_P$1") (pintype "bidirectional"))
      (node (ref "C4") (pin "P$2") (pinfunction "2_P$2") (pintype "bidirectional"))
      (node (ref "CON1") (pin "4") (pinfunction "VDD_4") (pintype "bidirectional"))
      (node (ref "IC1") (pin "C5") (pinfunction "VDD_C5") (pintype "power_in"))
      (node (ref "IC1") (pin "C7") (pinfunction "VDD_C7") (pintype "power_in"))
      (node (ref "IC1") (pin "C8") (pinfunction "VDD_C8") (pintype "power_in"))
      (node (ref "IC1") (pin "C9") (pinfunction "VDD_C9") (pintype "power_in"))
      (node (ref "IC1") (pin "F3") (pinfunction "VDD_F3") (pintype "power_in"))
      (node (ref "IC1") (pin "G13") (pinfunction "VDD_G13") (pintype "power_in"))
      (node (ref "IC1") (pin "G3") (pinfunction "VDD_G3") (pintype "power_in"))
      (node (ref "IC1") (pin "H13") (pinfunction "VDD_H13") (pintype "power_in"))
      (node (ref "IC1") (pin "J12") (pinfunction "VDD_J12") (pintype "power_in"))
      (node (ref "IC1") (pin "J13") (pinfunction "VDD_J13") (pintype "power_in"))
      (node (ref "IC1") (pin "K4") (pinfunction "VDD_K4") (pintype "power_in"))
      (node (ref "IC1") (pin "N10") (pinfunction "VDD_N10") (pintype "power_in"))
      (node (ref "IC1") (pin "N8") (pinfunction "VDD_N8") (pintype "power_in"))
      (node (ref "IC1") (pin "N9") (pinfunction "VDD_N9") (pintype "power_in"))
      (node (ref "R4") (pin "P$2") (pinfunction "2_P$2") (pintype "bidirectional"))
      (node (ref "U2") (pin "9") (pinfunction "VOUT_9") (pintype "bidirectional"))
    )
    (net (code "53") (name "VDDA") (class "Default")
      (node (ref "IC1") (pin "R1") (pinfunction "VDDA_R1") (pintype "power_in"))
    )
    (net (code "54") (name "VREF+") (class "Default")
      (node (ref "IC1") (pin "P1") (pinfunction "VREF+_P1") (pintype "power_in"))
    )
    (net (code "55") (name "VREF-") (class "Default")
      (node (ref "IC1") (pin "N1") (pinfunction "VREF-_N1") (pintype "power_in"))
    )
    (net (code "56") (name "VSSA") (class "Default")
      (node (ref "IC1") (pin "M1") (pinfunction "VSSA_M1") (pintype "power_in"))
    )
    (net (code "57") (name "unconnected-(CON1-NC-Pad35)") (class "Default")
      (node (ref "CON1") (pin "35") (pinfunction "NC_35") (pintype "bidirectional"))
    )
    (net (code "58") (name "unconnected-(CON1-NC-Pad37)") (class "Default")
      (node (ref "CON1") (pin "37") (pinfunction "NC_37") (pintype "bidirectional"))
    )
    (net (code "59") (name "unconnected-(CON1-NC-Pad38)") (class "Default")
      (node (ref "CON1") (pin "38") (pinfunction "NC_38") (pintype "bidirectional"))
    )
    (net (code "60") (name "unconnected-(CON1-NC-Pad39)") (class "Default")
      (node (ref "CON1") (pin "39") (pinfunction "NC_39") (pintype "bidirectional"))
    )
    (net (code "61") (name "unconnected-(CON1-NC-Pad40)") (class "Default")
      (node (ref "CON1") (pin "40") (pinfunction "NC_40") (pintype "bidirectional"))
    )
    (net (code "62") (name "unconnected-(IC1A-BOOT0-PadD6)") (class "Default")
      (node (ref "IC1") (pin "D6") (pinfunction "BOOT0_D6") (pintype "input"))
    )
    (net (code "63") (name "unconnected-(IC1A-BYPASS_REG-PadL4)") (class "Default")
      (node (ref "IC1") (pin "L4") (pinfunction "BYPASS_REG_L4") (pintype "input"))
    )
    (net (code "64") (name "unconnected-(IC1A-NRST-PadJ1)") (class "Default")
      (node (ref "IC1") (pin "J1") (pinfunction "NRST_J1") (pintype "bidirectional"))
    )
    (net (code "65") (name "unconnected-(IC1A-OSC_IN-PadG1)") (class "Default")
      (node (ref "IC1") (pin "G1") (pinfunction "OSC_IN_G1") (pintype "bidirectional"))
    )
    (net (code "66") (name "unconnected-(IC1A-OSC_OUT-PadH1)") (class "Default")
      (node (ref "IC1") (pin "H1") (pinfunction "OSC_OUT_H1") (pintype "bidirectional"))
    )
    (net (code "67") (name "unconnected-(IC1A-PA0-PadN3)") (class "Default")
      (node (ref "IC1") (pin "N3") (pinfunction "PA0_N3") (pintype "bidirectional"))
    )
    (net (code "68") (name "unconnected-(IC1A-PA7-PadR3)") (class "Default")
      (node (ref "IC1") (pin "R3") (pinfunction "PA7_R3") (pintype "bidirectional"))
    )
    (net (code "69") (name "unconnected-(IC1A-PA9-PadE15)") (class "Default")
      (node (ref "IC1") (pin "E15") (pinfunction "PA9_E15") (pintype "bidirectional"))
    )
    (net (code "70") (name "unconnected-(IC1A-PA10-PadD15)") (class "Default")
      (node (ref "IC1") (pin "D15") (pinfunction "PA10_D15") (pintype "bidirectional"))
    )
    (net (code "71") (name "unconnected-(IC1A-PA13-PadA15)") (class "Default")
      (node (ref "IC1") (pin "A15") (pinfunction "PA13_A15") (pintype "bidirectional"))
    )
    (net (code "72") (name "unconnected-(IC1A-PA14-PadA14)") (class "Default")
      (node (ref "IC1") (pin "A14") (pinfunction "PA14_A14") (pintype "bidirectional"))
    )
    (net (code "73") (name "unconnected-(IC1A-PA15-PadA13)") (class "Default")
      (node (ref "IC1") (pin "A13") (pinfunction "PA15_A13") (pintype "bidirectional"))
    )
    (net (code "74") (name "unconnected-(IC1A-PB2-PadM6)") (class "Default")
      (node (ref "IC1") (pin "M6") (pinfunction "PB2_M6") (pintype "bidirectional"))
    )
    (net (code "75") (name "unconnected-(IC1A-PB3-PadA10)") (class "Default")
      (node (ref "IC1") (pin "A10") (pinfunction "PB3_A10") (pintype "bidirectional"))
    )
    (net (code "76") (name "unconnected-(IC1A-PB4-PadA9)") (class "Default")
      (node (ref "IC1") (pin "A9") (pinfunction "PB4_A9") (pintype "bidirectional"))
    )
    (net (code "77") (name "unconnected-(IC1A-PB6-PadB6)") (class "Default")
      (node (ref "IC1") (pin "B6") (pinfunction "PB6_B6") (pintype "bidirectional"))
    )
    (net (code "78") (name "unconnected-(IC1A-PB7-PadB5)") (class "Default")
      (node (ref "IC1") (pin "B5") (pinfunction "PB7_B5") (pintype "bidirectional"))
    )
    (net (code "79") (name "unconnected-(IC1A-PB12-PadP12)") (class "Default")
      (node (ref "IC1") (pin "P12") (pinfunction "PB12_P12") (pintype "bidirectional"))
    )
    (net (code "80") (name "unconnected-(IC1A-PB13-PadP13)") (class "Default")
      (node (ref "IC1") (pin "P13") (pinfunction "PB13_P13") (pintype "bidirectional"))
    )
    (net (code "81") (name "unconnected-(IC1A-PB14-PadR14)") (class "Default")
      (node (ref "IC1") (pin "R14") (pinfunction "PB14_R14") (pintype "bidirectional"))
    )
    (net (code "82") (name "unconnected-(IC1A-PB15-PadR15)") (class "Default")
      (node (ref "IC1") (pin "R15") (pinfunction "PB15_R15") (pintype "bidirectional"))
    )
    (net (code "83") (name "unconnected-(IC1A-PC1-PadM3)") (class "Default")
      (node (ref "IC1") (pin "M3") (pinfunction "PC1_M3") (pintype "bidirectional"))
    )
    (net (code "84") (name "unconnected-(IC1A-PC2-PadM4)") (class "Default")
      (node (ref "IC1") (pin "M4") (pinfunction "PC2_M4") (pintype "bidirectional"))
    )
    (net (code "85") (name "unconnected-(IC1A-PC3-PadM5)") (class "Default")
      (node (ref "IC1") (pin "M5") (pinfunction "PC3_M5") (pintype "bidirectional"))
    )
    (net (code "86") (name "unconnected-(IC1A-PC4-PadN5)") (class "Default")
      (node (ref "IC1") (pin "N5") (pinfunction "PC4_N5") (pintype "bidirectional"))
    )
    (net (code "87") (name "unconnected-(IC1A-PC5-PadP5)") (class "Default")
      (node (ref "IC1") (pin "P5") (pinfunction "PC5_P5") (pintype "bidirectional"))
    )
    (net (code "88") (name "unconnected-(IC1A-PC8-PadG14)") (class "Default")
      (node (ref "IC1") (pin "G14") (pinfunction "PC8_G14") (pintype "bidirectional"))
    )
    (net (code "89") (name "unconnected-(IC1A-PC9-PadF14)") (class "Default")
      (node (ref "IC1") (pin "F14") (pinfunction "PC9_F14") (pintype "bidirectional"))
    )
    (net (code "90") (name "unconnected-(IC1A-PC11-PadB13)") (class "Default")
      (node (ref "IC1") (pin "B13") (pinfunction "PC11_B13") (pintype "bidirectional"))
    )
    (net (code "91") (name "unconnected-(IC1A-PC12-PadA12)") (class "Default")
      (node (ref "IC1") (pin "A12") (pinfunction "PC12_A12") (pintype "bidirectional"))
    )
    (net (code "92") (name "unconnected-(IC1A-PC13-PadD1)") (class "Default")
      (node (ref "IC1") (pin "D1") (pinfunction "PC13_D1") (pintype "bidirectional"))
    )
    (net (code "93") (name "unconnected-(IC1A-PC14-PadE1)") (class "Default")
      (node (ref "IC1") (pin "E1") (pinfunction "PC14_E1") (pintype "bidirectional"))
    )
    (net (code "94") (name "unconnected-(IC1A-PC15-PadF1)") (class "Default")
      (node (ref "IC1") (pin "F1") (pinfunction "PC15_F1") (pintype "bidirectional"))
    )
    (net (code "95") (name "unconnected-(IC1A-PD0-PadB12)") (class "Default")
      (node (ref "IC1") (pin "B12") (pinfunction "PD0_B12") (pintype "bidirectional"))
    )
    (net (code "96") (name "unconnected-(IC1A-PD1-PadC12)") (class "Default")
      (node (ref "IC1") (pin "C12") (pinfunction "PD1_C12") (pintype "bidirectional"))
    )
    (net (code "97") (name "unconnected-(IC1A-PD2-PadD12)") (class "Default")
      (node (ref "IC1") (pin "D12") (pinfunction "PD2_D12") (pintype "bidirectional"))
    )
    (net (code "98") (name "unconnected-(IC1A-PD4-PadD10)") (class "Default")
      (node (ref "IC1") (pin "D10") (pinfunction "PD4_D10") (pintype "bidirectional"))
    )
    (net (code "99") (name "unconnected-(IC1A-PD5-PadC11)") (class "Default")
      (node (ref "IC1") (pin "C11") (pinfunction "PD5_C11") (pintype "bidirectional"))
    )
    (net (code "100") (name "unconnected-(IC1A-PD7-PadA11)") (class "Default")
      (node (ref "IC1") (pin "A11") (pinfunction "PD7_A11") (pintype "bidirectional"))
    )
    (net (code "101") (name "unconnected-(IC1A-PD8-PadP15)") (class "Default")
      (node (ref "IC1") (pin "P15") (pinfunction "PD8_P15") (pintype "bidirectional"))
    )
    (net (code "102") (name "unconnected-(IC1A-PD9-PadP14)") (class "Default")
      (node (ref "IC1") (pin "P14") (pinfunction "PD9_P14") (pintype "bidirectional"))
    )
    (net (code "103") (name "unconnected-(IC1A-PD11-PadN14)") (class "Default")
      (node (ref "IC1") (pin "N14") (pinfunction "PD11_N14") (pintype "bidirectional"))
    )
    (net (code "104") (name "unconnected-(IC1A-PD12-PadN13)") (class "Default")
      (node (ref "IC1") (pin "N13") (pinfunction "PD12_N13") (pintype "bidirectional"))
    )
    (net (code "105") (name "unconnected-(IC1A-PD13-PadM15)") (class "Default")
      (node (ref "IC1") (pin "M15") (pinfunction "PD13_M15") (pintype "bidirectional"))
    )
    (net (code "106") (name "unconnected-(IC1A-PD14-PadM14)") (class "Default")
      (node (ref "IC1") (pin "M14") (pinfunction "PD14_M14") (pintype "bidirectional"))
    )
    (net (code "107") (name "unconnected-(IC1A-PD15-PadL14)") (class "Default")
      (node (ref "IC1") (pin "L14") (pinfunction "PD15_L14") (pintype "bidirectional"))
    )
    (net (code "108") (name "unconnected-(IC1A-PDR_ON-PadC6)") (class "Default")
      (node (ref "IC1") (pin "C6") (pinfunction "PDR_ON_C6") (pintype "input"))
    )
    (net (code "109") (name "unconnected-(IC1A-PE0-PadA4)") (class "Default")
      (node (ref "IC1") (pin "A4") (pinfunction "PE0_A4") (pintype "bidirectional"))
    )
    (net (code "110") (name "unconnected-(IC1A-PE1-PadA3)") (class "Default")
      (node (ref "IC1") (pin "A3") (pinfunction "PE1_A3") (pintype "bidirectional"))
    )
    (net (code "111") (name "unconnected-(IC1A-PE2-PadA2)") (class "Default")
      (node (ref "IC1") (pin "A2") (pinfunction "PE2_A2") (pintype "bidirectional"))
    )
    (net (code "112") (name "unconnected-(IC1A-PE3-PadA1)") (class "Default")
      (node (ref "IC1") (pin "A1") (pinfunction "PE3_A1") (pintype "bidirectional"))
    )
    (net (code "113") (name "unconnected-(IC1A-PE7-PadR8)") (class "Default")
      (node (ref "IC1") (pin "R8") (pinfunction "PE7_R8") (pintype "bidirectional"))
    )
    (net (code "114") (name "unconnected-(IC1A-PE8-PadP8)") (class "Default")
      (node (ref "IC1") (pin "P8") (pinfunction "PE8_P8") (pintype "bidirectional"))
    )
    (net (code "115") (name "unconnected-(IC1A-PE9-PadP9)") (class "Default")
      (node (ref "IC1") (pin "P9") (pinfunction "PE9_P9") (pintype "bidirectional"))
    )
    (net (code "116") (name "unconnected-(IC1A-PE10-PadR9)") (class "Default")
      (node (ref "IC1") (pin "R9") (pinfunction "PE10_R9") (pintype "bidirectional"))
    )
    (net (code "117") (name "unconnected-(IC1A-PF0-PadE2)") (class "Default")
      (node (ref "IC1") (pin "E2") (pinfunction "PF0_E2") (pintype "bidirectional"))
    )
    (net (code "118") (name "unconnected-(IC1A-PF1-PadH3)") (class "Default")
      (node (ref "IC1") (pin "H3") (pinfunction "PF1_H3") (pintype "bidirectional"))
    )
    (net (code "119") (name "unconnected-(IC1A-PF2-PadH2)") (class "Default")
      (node (ref "IC1") (pin "H2") (pinfunction "PF2_H2") (pintype "bidirectional"))
    )
    (net (code "120") (name "unconnected-(IC1A-PF3-PadJ2)") (class "Default")
      (node (ref "IC1") (pin "J2") (pinfunction "PF3_J2") (pintype "bidirectional"))
    )
    (net (code "121") (name "unconnected-(IC1A-PF4-PadJ3)") (class "Default")
      (node (ref "IC1") (pin "J3") (pinfunction "PF4_J3") (pintype "bidirectional"))
    )
    (net (code "122") (name "unconnected-(IC1A-PF5-PadK3)") (class "Default")
      (node (ref "IC1") (pin "K3") (pinfunction "PF5_K3") (pintype "bidirectional"))
    )
    (net (code "123") (name "unconnected-(IC1A-PF6-PadK2)") (class "Default")
      (node (ref "IC1") (pin "K2") (pinfunction "PF6_K2") (pintype "bidirectional"))
    )
    (net (code "124") (name "unconnected-(IC1A-PF7-PadK1)") (class "Default")
      (node (ref "IC1") (pin "K1") (pinfunction "PF7_K1") (pintype "bidirectional"))
    )
    (net (code "125") (name "unconnected-(IC1A-PF8-PadL3)") (class "Default")
      (node (ref "IC1") (pin "L3") (pinfunction "PF8_L3") (pintype "bidirectional"))
    )
    (net (code "126") (name "unconnected-(IC1A-PF9-PadL2)") (class "Default")
      (node (ref "IC1") (pin "L2") (pinfunction "PF9_L2") (pintype "bidirectional"))
    )
    (net (code "127") (name "unconnected-(IC1A-PF11-PadR6)") (class "Default")
      (node (ref "IC1") (pin "R6") (pinfunction "PF11_R6") (pintype "bidirectional"))
    )
    (net (code "128") (name "unconnected-(IC1A-PF12-PadP6)") (class "Default")
      (node (ref "IC1") (pin "P6") (pinfunction "PF12_P6") (pintype "bidirectional"))
    )
    (net (code "129") (name "unconnected-(IC1A-PF13-PadN6)") (class "Default")
      (node (ref "IC1") (pin "N6") (pinfunction "PF13_N6") (pintype "bidirectional"))
    )
    (net (code "130") (name "unconnected-(IC1A-PF14-PadR7)") (class "Default")
      (node (ref "IC1") (pin "R7") (pinfunction "PF14_R7") (pintype "bidirectional"))
    )
    (net (code "131") (name "unconnected-(IC1A-PF15-PadP7)") (class "Default")
      (node (ref "IC1") (pin "P7") (pinfunction "PF15_P7") (pintype "bidirectional"))
    )
    (net (code "132") (name "unconnected-(IC1A-PG0-PadN7)") (class "Default")
      (node (ref "IC1") (pin "N7") (pinfunction "PG0_N7") (pintype "bidirectional"))
    )
    (net (code "133") (name "unconnected-(IC1A-PG1-PadM7)") (class "Default")
      (node (ref "IC1") (pin "M7") (pinfunction "PG1_M7") (pintype "bidirectional"))
    )
    (net (code "134") (name "unconnected-(IC1A-PG2-PadL15)") (class "Default")
      (node (ref "IC1") (pin "L15") (pinfunction "PG2_L15") (pintype "bidirectional"))
    )
    (net (code "135") (name "unconnected-(IC1A-PG3-PadK15)") (class "Default")
      (node (ref "IC1") (pin "K15") (pinfunction "PG3_K15") (pintype "bidirectional"))
    )
    (net (code "136") (name "unconnected-(IC1A-PG4-PadK14)") (class "Default")
      (node (ref "IC1") (pin "K14") (pinfunction "PG4_K14") (pintype "bidirectional"))
    )
    (net (code "137") (name "unconnected-(IC1A-PG5-PadK13)") (class "Default")
      (node (ref "IC1") (pin "K13") (pinfunction "PG5_K13") (pintype "bidirectional"))
    )
    (net (code "138") (name "unconnected-(IC1A-PG9-PadC10)") (class "Default")
      (node (ref "IC1") (pin "C10") (pinfunction "PG9_C10") (pintype "bidirectional"))
    )
    (net (code "139") (name "unconnected-(IC1A-PG15-PadB7)") (class "Default")
      (node (ref "IC1") (pin "B7") (pinfunction "PG15_B7") (pintype "bidirectional"))
    )
    (net (code "140") (name "unconnected-(IC1A-PH5-PadJ4)") (class "Default")
      (node (ref "IC1") (pin "J4") (pinfunction "PH5_J4") (pintype "bidirectional"))
    )
    (net (code "141") (name "unconnected-(IC1A-PH6-PadM11)") (class "Default")
      (node (ref "IC1") (pin "M11") (pinfunction "PH6_M11") (pintype "bidirectional"))
    )
    (net (code "142") (name "unconnected-(IC1A-PH7-PadN12)") (class "Default")
      (node (ref "IC1") (pin "N12") (pinfunction "PH7_N12") (pintype "bidirectional"))
    )
    (net (code "143") (name "unconnected-(IC1A-PI3-PadC13)") (class "Default")
      (node (ref "IC1") (pin "C13") (pinfunction "PI3_C13") (pintype "bidirectional"))
    )
    (net (code "144") (name "unconnected-(IC1A-PI8-PadD2)") (class "Default")
      (node (ref "IC1") (pin "D2") (pinfunction "PI8_D2") (pintype "bidirectional"))
    )
    (net (code "145") (name "unconnected-(IC1A-PI11-PadE4)") (class "Default")
      (node (ref "IC1") (pin "E4") (pinfunction "PI11_E4") (pintype "bidirectional"))
    )
    (net (code "146") (name "unconnected-(JP1-Pad1)") (class "Default")
      (node (ref "JP1") (pin "1") (pinfunction "1_1") (pintype "passive"))
    )
    (net (code "147") (name "unconnected-(JP1-Pad2)") (class "Default")
      (node (ref "JP1") (pin "2") (pinfunction "2_2") (pintype "passive"))
    )
    (net (code "148") (name "unconnected-(JP1-Pad3)") (class "Default")
      (node (ref "JP1") (pin "3") (pinfunction "3_3") (pintype "passive"))
    )
    (net (code "149") (name "unconnected-(JP1-Pad4)") (class "Default")
      (node (ref "JP1") (pin "4") (pinfunction "4_4") (pintype "passive"))
    )
    (net (code "150") (name "unconnected-(JP1-Pad5)") (class "Default")
      (node (ref "JP1") (pin "5") (pinfunction "5_5") (pintype "passive"))
    )
    (net (code "151") (name "unconnected-(JP1-Pad6)") (class "Default")
      (node (ref "JP1") (pin "6") (pinfunction "6_6") (pintype "passive"))
    )
    (net (code "152") (name "unconnected-(JP1-Pad7)") (class "Default")
      (node (ref "JP1") (pin "7") (pinfunction "7_7") (pintype "passive"))
    )
    (net (code "153") (name "unconnected-(JP1-Pad8)") (class "Default")
      (node (ref "JP1") (pin "8") (pinfunction "8_8") (pintype "passive"))
    )
    (net (code "154") (name "unconnected-(JP1-Pad9)") (class "Default")
      (node (ref "JP1") (pin "9") (pinfunction "9_9") (pintype "passive"))
    )
    (net (code "155") (name "unconnected-(JP1-Pad10)") (class "Default")
      (node (ref "JP1") (pin "10") (pinfunction "10_10") (pintype "passive"))
    )
    (net (code "156") (name "unconnected-(U1-PG-Pad5)") (class "Default")
      (node (ref "U1") (pin "5") (pinfunction "PG_5") (pintype "bidirectional"))
    )
    (net (code "157") (name "unconnected-(U2-PG-Pad5)") (class "Default")
      (node (ref "U2") (pin "5") (pinfunction "PG_5") (pintype "bidirectional"))
    )
  )
)
